# STM32C8.net
KiCad netlist of a schematic drawn in Altium Designer
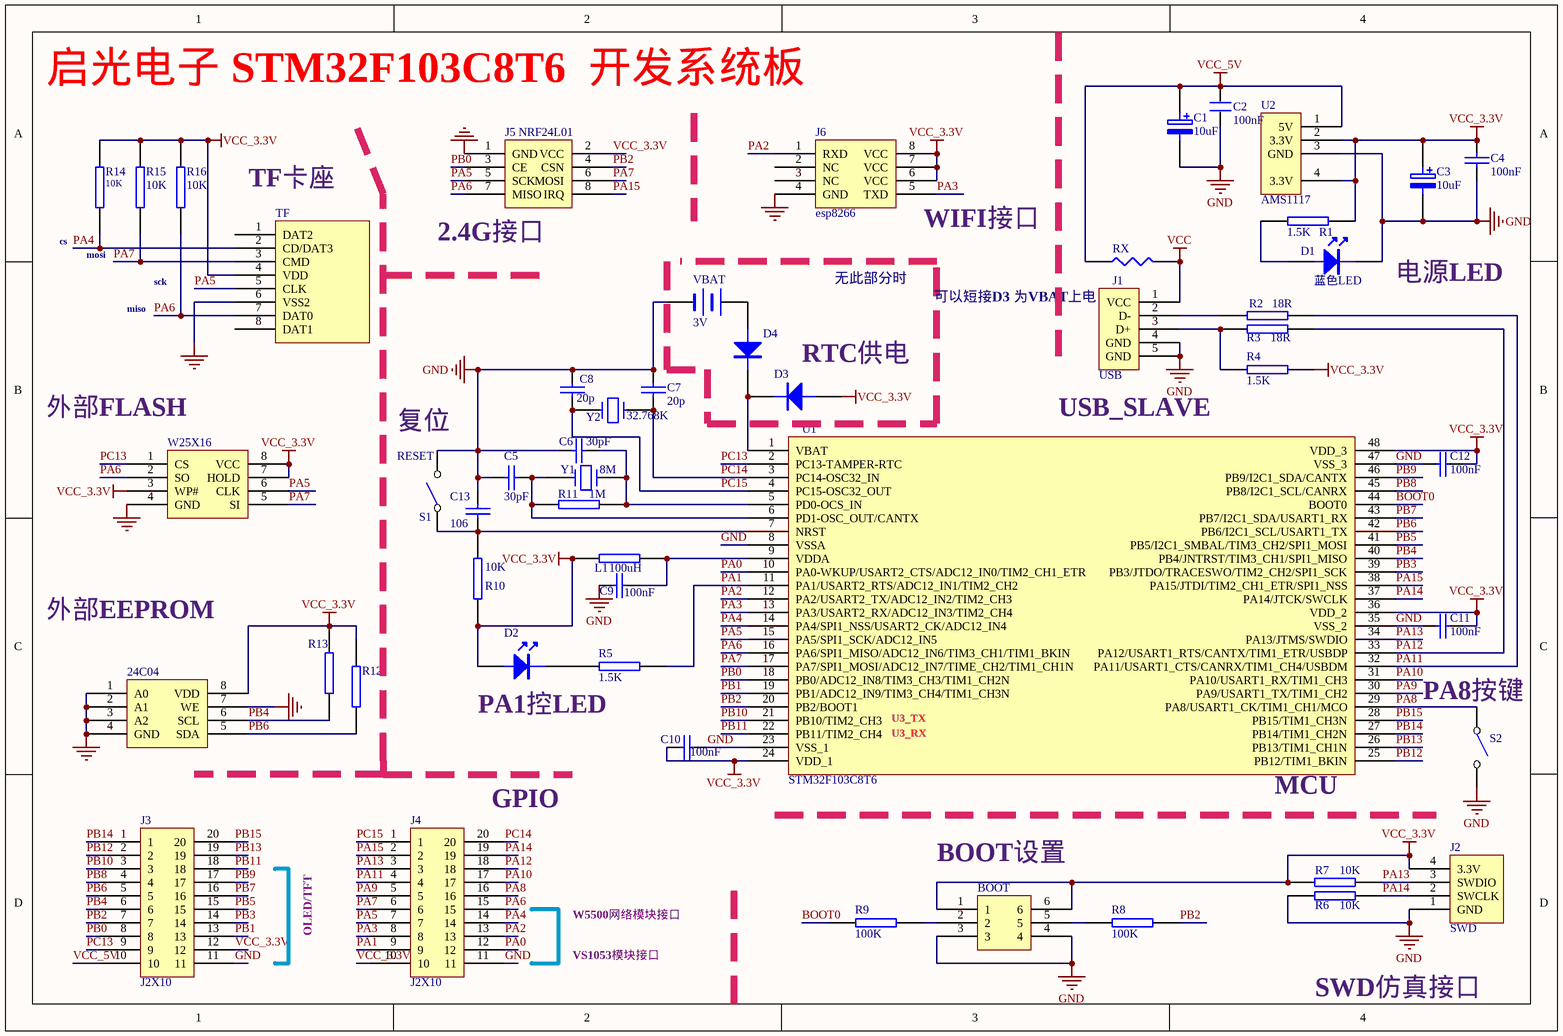
[diagram p0: STM32C8 原理图.SchDoc]

(export (version "E")
  (design (tool "Eeschema 10.0.6"))
  (components
    (comp (ref "24C04") (value "~") (footprint "STC15") (libsource (lib "*") (part "24C")))
    (comp (ref "BOOT") (value "~") (footprint "PZ2*3") (libsource (lib "*") (part "BOOT")))
    (comp (ref "C1")
      (value "10uF")
      (footprint "3216z")
      (description "Electrolytic Capacitor")
      (libsource (lib "原理图器件库(1)") (part "ELECTRO2"))
    )
    (comp (ref "C2") (value "100nF") (footprint "0603C1") (libsource (lib "原理图器件库(1)") (part "C")))
    (comp (ref "C3")
      (value "10uF")
      (footprint "3216z")
      (description "Electrolytic Capacitor")
      (libsource (lib "原理图器件库(1)") (part "ELECTRO2"))
    )
    (comp (ref "C4")
      (value "100nF")
      (footprint "0603C1")
      (description "Capacitor")
      (libsource (lib "原理图器件库") (part "CAP"))
    )
    (comp (ref "C5")
      (value "30pF")
      (footprint "0603C1")
      (description "Capacitor")
      (libsource (lib "*") (part "CAP"))
    )
    (comp (ref "C6")
      (value "30pF")
      (footprint "0603C1")
      (description "Capacitor")
      (libsource (lib "*") (part "CAP"))
    )
    (comp (ref "C7")
      (value "20p")
      (footprint "0603C1")
      (description "Capacitor")
      (libsource (lib "*") (part "CAP"))
    )
    (comp (ref "C8")
      (value "20p")
      (footprint "0603C1")
      (description "Capacitor")
      (libsource (lib "*") (part "CAP"))
    )
    (comp (ref "C9")
      (value "100nF")
      (footprint "0603C1")
      (description "Capacitor")
      (libsource (lib "*") (part "CAP"))
    )
    (comp (ref "C10")
      (value "100nF")
      (footprint "0603C1")
      (description "Capacitor")
      (libsource (lib "*") (part "CAP"))
    )
    (comp (ref "C11")
      (value "100nF")
      (footprint "0603C1")
      (description "Capacitor")
      (libsource (lib "原理图器件库") (part "CAP"))
    )
    (comp (ref "C12")
      (value "100nF")
      (footprint "0603C1")
      (description "Capacitor")
      (libsource (lib "原理图器件库") (part "CAP"))
    )
    (comp (ref "C13")
      (value "106")
      (footprint "0603C1")
      (description "Capacitor")
      (libsource (lib "*") (part "CAP"))
    )
    (comp (ref "D1") (value "蓝色LED") (footprint "LED") (libsource (lib "*") (part "D")))
    (comp (ref "D2") (value "~") (footprint "LED") (libsource (lib "*") (part "D")))
    (comp (ref "D3")
      (value "~")
      (footprint "1206Z")
      (description "Diode")
      (libsource (lib "*") (part "DIODE"))
    )
    (comp (ref "D4")
      (value "~")
      (footprint "1206Z")
      (description "Diode")
      (libsource (lib "*") (part "DIODE"))
    )
    (comp (ref "J1") (value "USB") (footprint "micro-dip") (libsource (lib "原理图器件库(1)") (part "USB")))
    (comp (ref "J2") (value "SWD") (footprint "90p4pz") (libsource (lib "原理图器件库(1)") (part "JSWD")))
    (comp (ref "J3") (value "J2X10") (footprint "PZ2X10") (libsource (lib "原理图器件库(1)") (part "J2X10")))
    (comp (ref "J4") (value "J2X10") (footprint "PZ2X10") (libsource (lib "原理图器件库(1)") (part "J2X10")))
    (comp (ref "J5") (value "NRF24L01") (footprint "NRF24L01") (libsource (lib "*") (part "NRF24L01")))
    (comp (ref "J6") (value "esp8266") (libsource (lib "原理图器件库(1)") (part "esp8266")))
    (comp (ref "L1") (value "100uH") (footprint "0805z") (libsource (lib "*") (part "RES2")))
    (comp (ref "R1") (value "1.5K") (footprint "0603R1") (libsource (lib "*") (part "RES2")))
    (comp (ref "R2") (value "18R") (footprint "0603R1") (libsource (lib "*") (part "RES2")))
    (comp (ref "R3") (value "18R") (footprint "0603R1") (libsource (lib "*") (part "RES2")))
    (comp (ref "R4") (value "1.5K") (footprint "0603R1") (libsource (lib "*") (part "RES2")))
    (comp (ref "R5") (value "1.5K") (footprint "0603R1") (libsource (lib "*") (part "RES2")))
    (comp (ref "R6") (value "10K") (footprint "0603R1") (libsource (lib "*") (part "RES2")))
    (comp (ref "R7") (value "10K") (footprint "0603R1") (libsource (lib "*") (part "RES2")))
    (comp (ref "R8") (value "100K") (footprint "0603R1") (libsource (lib "*") (part "RES2")))
    (comp (ref "R9") (value "100K") (footprint "0603R1") (libsource (lib "*") (part "RES2")))
    (comp (ref "R10") (value "10K") (footprint "0603R1") (libsource (lib "*") (part "RES2")))
    (comp (ref "R11") (value "1M") (footprint "0603R1") (libsource (lib "*") (part "RES2")))
    (comp (ref "R12") (value "~") (footprint "0603R1") (libsource (lib "*") (part "RES2")))
    (comp (ref "R13") (value "~") (footprint "0603R1") (libsource (lib "*") (part "RES2")))
    (comp (ref "R14") (value "10K") (footprint "0805Z") (libsource (lib "*") (part "RES2")))
    (comp (ref "R15") (value "10K") (footprint "0805Z") (libsource (lib "*") (part "RES2")))
    (comp (ref "R16") (value "10K") (footprint "0805Z") (libsource (lib "*") (part "RES2")))
    (comp (ref "RX") (value "~") (footprint "1206z") (libsource (lib "*") (part "RES1")))
    (comp (ref "S1") (value "~") (footprint "FWAJ") (libsource (lib "*") (part "SW-SPST")))
    (comp (ref "S2") (value "~") (footprint "FWAJ") (libsource (lib "*") (part "SW-SPST")))
    (comp (ref "TF") (value "~") (footprint "TF") (libsource (lib "*") (part "MINISD")))
    (comp (ref "U1")
      (value "STM32F103C8T6")
      (footprint "STC12-48")
      (libsource (lib "原理图器件库(1)") (part "STM32C8T6"))
    )
    (comp (ref "U2") (value "AMS1117") (footprint "AMS1117") (libsource (lib "原理图器件库(1)") (part "AMS1117")))
    (comp (ref "VBAT")
      (value "3V")
      (footprint "CR1220")
      (description "Battery")
      (libsource (lib "*") (part "BATTERY"))
    )
    (comp (ref "W25X16") (value "~") (footprint "W25X16") (libsource (lib "*") (part "W25X16")))
    (comp (ref "Y1")
      (value "8M")
      (footprint "YT")
      (description "Crystal")
      (libsource (lib "*") (part "CRYSTAL"))
    )
    (comp (ref "Y2")
      (value "32.768K")
      (footprint "32.768kt")
      (description "Crystal")
      (libsource (lib "*") (part "CRYSTAL"))
    )
  )
  (nets
    (net (code "1") (name "/BOOT0") (class "Default")
      (node (ref "R9") (pin "2") (pinfunction "2_2") (pintype "passive"))
      (node (ref "U1") (pin "44") (pinfunction "BOOT0_44") (pintype "passive"))
    )
    (net (code "2") (name "/PA0") (class "Default")
      (node (ref "J4") (pin "12") (pinfunction "12_12") (pintype "passive"))
      (node (ref "U1") (pin "10") (pinfunction "PA0-WKUP/USART2_CTS/ADC12_IN0/TIM2_CH1_ETR_10") (pintype "passive"))
    )
    (net (code "3") (name "/PA1") (class "Default")
      (node (ref "J4") (pin "9") (pinfunction "9_9") (pintype "passive"))
      (node (ref "R5") (pin "1") (pinfunction "1_1") (pintype "passive"))
      (node (ref "U1") (pin "11") (pinfunction "PA1/USART2_RTS/ADC12_IN1/TIM2_CH2_11") (pintype "passive"))
    )
    (net (code "4") (name "/PA2") (class "Default")
      (node (ref "J4") (pin "13") (pinfunction "13_13") (pintype "passive"))
      (node (ref "J6") (pin "1") (pinfunction "RXD_1") (pintype "passive"))
      (node (ref "U1") (pin "12") (pinfunction "PA2/USART2_TX/ADC12_IN2/TIM2_CH3_12") (pintype "passive"))
    )
    (net (code "5") (name "/PA3") (class "Default")
      (node (ref "J4") (pin "8") (pinfunction "8_8") (pintype "passive"))
      (node (ref "J6") (pin "5") (pinfunction "TXD_5") (pintype "passive"))
      (node (ref "U1") (pin "13") (pinfunction "PA3/USART2_RX/ADC12_IN3/TIM2_CH4_13") (pintype "passive"))
    )
    (net (code "6") (name "/PA4") (class "Default")
      (node (ref "J4") (pin "14") (pinfunction "14_14") (pintype "passive"))
      (node (ref "R14") (pin "2") (pinfunction "2_2") (pintype "passive"))
      (node (ref "TF") (pin "2") (pinfunction "CD/DAT3_2") (pintype "passive"))
      (node (ref "U1") (pin "14") (pinfunction "PA4/SPI1_NSS/USART2_CK/ADC12_IN4_14") (pintype "passive"))
    )
    (net (code "7") (name "/PA5") (class "Default")
      (node (ref "J4") (pin "7") (pinfunction "7_7") (pintype "passive"))
      (node (ref "J5") (pin "5") (pinfunction "SCK_5") (pintype "passive"))
      (node (ref "TF") (pin "5") (pinfunction "CLK_5") (pintype "passive"))
      (node (ref "U1") (pin "15") (pinfunction "PA5/SPI1_SCK/ADC12_IN5_15") (pintype "passive"))
      (node (ref "W25X16") (pin "6") (pinfunction "CLK_6") (pintype "passive"))
    )
    (net (code "8") (name "/PA6") (class "Default")
      (node (ref "J4") (pin "15") (pinfunction "15_15") (pintype "passive"))
      (node (ref "J5") (pin "7") (pinfunction "MISO_7") (pintype "passive"))
      (node (ref "R16") (pin "2") (pinfunction "2_2") (pintype "passive"))
      (node (ref "TF") (pin "7") (pinfunction "DAT0_7") (pintype "passive"))
      (node (ref "U1") (pin "16") (pinfunction "PA6/SPI1_MISO/ADC12_IN6/TIM3_CH1/TIM1_BKIN_16") (pintype "passive"))
      (node (ref "W25X16") (pin "2") (pinfunction "SO_2") (pintype "passive"))
    )
    (net (code "9") (name "/PA7") (class "Default")
      (node (ref "J4") (pin "6") (pinfunction "6_6") (pintype "passive"))
      (node (ref "J5") (pin "6") (pinfunction "MOSI_6") (pintype "passive"))
      (node (ref "R15") (pin "2") (pinfunction "2_2") (pintype "passive"))
      (node (ref "TF") (pin "3") (pinfunction "CMD_3") (pintype "passive"))
      (node (ref "U1") (pin "17") (pinfunction "PA7/SPI1_MOSI/ADC12_IN7/TIME_CH2/TIM1_CH1N_17") (pintype "passive"))
      (node (ref "W25X16") (pin "5") (pinfunction "SI_5") (pintype "passive"))
    )
    (net (code "10") (name "/PA8") (class "Default")
      (node (ref "J4") (pin "16") (pinfunction "16_16") (pintype "passive"))
      (node (ref "S2") (pin "1") (pinfunction "1_1") (pintype "passive"))
      (node (ref "U1") (pin "29") (pinfunction "PA8/USART1_CK/TIM1_CH1/MCO_29") (pintype "passive"))
    )
    (net (code "11") (name "/PA9") (class "Default")
      (node (ref "J4") (pin "5") (pinfunction "5_5") (pintype "passive"))
      (node (ref "U1") (pin "30") (pinfunction "PA9/USART1_TX/TIM1_CH2_30") (pintype "passive"))
    )
    (net (code "12") (name "/PA10") (class "Default")
      (node (ref "J4") (pin "17") (pinfunction "17_17") (pintype "passive"))
      (node (ref "U1") (pin "31") (pinfunction "PA10/USART1_RX/TIM1_CH3_31") (pintype "passive"))
    )
    (net (code "13") (name "/PA11") (class "Default")
      (node (ref "J4") (pin "4") (pinfunction "4_4") (pintype "passive"))
      (node (ref "R2") (pin "2") (pinfunction "2_2") (pintype "passive"))
      (node (ref "U1") (pin "32") (pinfunction "PA11/USART1_CTS/CANRX/TIM1_CH4/USBDM_32") (pintype "passive"))
    )
    (net (code "14") (name "/PA12") (class "Default")
      (node (ref "J4") (pin "18") (pinfunction "18_18") (pintype "passive"))
      (node (ref "R3") (pin "2") (pinfunction "2_2") (pintype "passive"))
      (node (ref "U1") (pin "33") (pinfunction "PA12/USART1_RTS/CANTX/TIM1_ETR/USBDP_33") (pintype "passive"))
    )
    (net (code "15") (name "/PA13") (class "Default")
      (node (ref "J2") (pin "3") (pinfunction "SWDIO_3") (pintype "passive"))
      (node (ref "J4") (pin "3") (pinfunction "3_3") (pintype "passive"))
      (node (ref "R7") (pin "2") (pinfunction "2_2") (pintype "passive"))
      (node (ref "U1") (pin "34") (pinfunction "PA13/JTMS/SWDIO_34") (pintype "passive"))
    )
    (net (code "16") (name "/PA14") (class "Default")
      (node (ref "J2") (pin "2") (pinfunction "SWCLK_2") (pintype "passive"))
      (node (ref "J4") (pin "19") (pinfunction "19_19") (pintype "passive"))
      (node (ref "R6") (pin "2") (pinfunction "2_2") (pintype "passive"))
      (node (ref "U1") (pin "37") (pinfunction "PA14/JTCK/SWCLK_37") (pintype "passive"))
    )
    (net (code "17") (name "/PA15") (class "Default")
      (node (ref "J4") (pin "2") (pinfunction "2_2") (pintype "passive"))
      (node (ref "J5") (pin "8") (pinfunction "IRQ_8") (pintype "passive"))
      (node (ref "U1") (pin "38") (pinfunction "PA15/JTDI/TIM2_CH1_ETR/SPI1_NSS_38") (pintype "passive"))
    )
    (net (code "18") (name "/PB0") (class "Default")
      (node (ref "J3") (pin "8") (pinfunction "8_8") (pintype "passive"))
      (node (ref "J5") (pin "3") (pinfunction "CE_3") (pintype "passive"))
      (node (ref "U1") (pin "18") (pinfunction "PB0/ADC12_IN8/TIM3_CH3/TIM1_CH2N_18") (pintype "passive"))
    )
    (net (code "19") (name "/PB1") (class "Default")
      (node (ref "J3") (pin "13") (pinfunction "13_13") (pintype "passive"))
      (node (ref "U1") (pin "19") (pinfunction "PB1/ADC12_IN9/TIM3_CH4/TIM1_CH3N_19") (pintype "passive"))
    )
    (net (code "20") (name "/PB2") (class "Default")
      (node (ref "J3") (pin "7") (pinfunction "7_7") (pintype "passive"))
      (node (ref "J5") (pin "4") (pinfunction "CSN_4") (pintype "passive"))
      (node (ref "R8") (pin "2") (pinfunction "2_2") (pintype "passive"))
      (node (ref "U1") (pin "20") (pinfunction "PB2/BOOT1_20") (pintype "passive"))
    )
    (net (code "21") (name "/PB3") (class "Default")
      (node (ref "J3") (pin "14") (pinfunction "14_14") (pintype "passive"))
      (node (ref "U1") (pin "39") (pinfunction "PB3/JTDO/TRACESWO/TIM2_CH2/SPI1_SCK_39") (pintype "passive"))
    )
    (net (code "22") (name "/PB4") (class "Default")
      (node (ref "24C04") (pin "6") (pinfunction "SCL_6") (pintype "passive"))
      (node (ref "J3") (pin "6") (pinfunction "6_6") (pintype "passive"))
      (node (ref "R13") (pin "1") (pinfunction "1_1") (pintype "passive"))
      (node (ref "U1") (pin "40") (pinfunction "PB4/JNTRST/TIM3_CH1/SPI1_MISO_40") (pintype "passive"))
    )
    (net (code "23") (name "/PB5") (class "Default")
      (node (ref "J3") (pin "15") (pinfunction "15_15") (pintype "passive"))
      (node (ref "U1") (pin "41") (pinfunction "PB5/I2C1_SMBAL/TIM3_CH2/SPI1_MOSI_41") (pintype "passive"))
    )
    (net (code "24") (name "/PB6") (class "Default")
      (node (ref "24C04") (pin "5") (pinfunction "SDA_5") (pintype "passive"))
      (node (ref "J3") (pin "5") (pinfunction "5_5") (pintype "passive"))
      (node (ref "R12") (pin "1") (pinfunction "1_1") (pintype "passive"))
      (node (ref "U1") (pin "42") (pinfunction "PB6/I2C1_SCL/USART1_TX_42") (pintype "passive"))
    )
    (net (code "25") (name "/PB7") (class "Default")
      (node (ref "J3") (pin "16") (pinfunction "16_16") (pintype "passive"))
      (node (ref "U1") (pin "43") (pinfunction "PB7/I2C1_SDA/USART1_RX_43") (pintype "passive"))
    )
    (net (code "26") (name "/PB8") (class "Default")
      (node (ref "J3") (pin "4") (pinfunction "4_4") (pintype "passive"))
      (node (ref "U1") (pin "45") (pinfunction "PB8/I2C1_SCL/CANRX_45") (pintype "passive"))
    )
    (net (code "27") (name "/PB9") (class "Default")
      (node (ref "J3") (pin "17") (pinfunction "17_17") (pintype "passive"))
      (node (ref "U1") (pin "46") (pinfunction "PB9/I2C1_SDA/CANTX_46") (pintype "passive"))
    )
    (net (code "28") (name "/PB10") (class "Default")
      (node (ref "J3") (pin "3") (pinfunction "3_3") (pintype "passive"))
      (node (ref "U1") (pin "21") (pinfunction "PB10/TIM2_CH3_21") (pintype "passive"))
    )
    (net (code "29") (name "/PB11") (class "Default")
      (node (ref "J3") (pin "18") (pinfunction "18_18") (pintype "passive"))
      (node (ref "U1") (pin "22") (pinfunction "PB11/TIM2_CH4_22") (pintype "passive"))
    )
    (net (code "30") (name "/PB12") (class "Default")
      (node (ref "J3") (pin "2") (pinfunction "2_2") (pintype "passive"))
      (node (ref "U1") (pin "25") (pinfunction "PB12/TIM1_BKIN_25") (pintype "passive"))
    )
    (net (code "31") (name "/PB13") (class "Default")
      (node (ref "J3") (pin "19") (pinfunction "19_19") (pintype "passive"))
      (node (ref "U1") (pin "26") (pinfunction "PB13/TIM1_CH1N_26") (pintype "passive"))
    )
    (net (code "32") (name "/PB14") (class "Default")
      (node (ref "J3") (pin "1") (pinfunction "1_1") (pintype "passive"))
      (node (ref "U1") (pin "27") (pinfunction "PB14/TIM1_CH2N_27") (pintype "passive"))
    )
    (net (code "33") (name "/PB15") (class "Default")
      (node (ref "J3") (pin "20") (pinfunction "20_20") (pintype "passive"))
      (node (ref "U1") (pin "28") (pinfunction "PB15/TIM1_CH3N_28") (pintype "passive"))
    )
    (net (code "34") (name "/PC13") (class "Default")
      (node (ref "J3") (pin "9") (pinfunction "9_9") (pintype "passive"))
      (node (ref "U1") (pin "2") (pinfunction "PC13-TAMPER-RTC_2") (pintype "passive"))
      (node (ref "W25X16") (pin "1") (pinfunction "CS_1") (pintype "passive"))
    )
    (net (code "35") (name "/PC14") (class "Default")
      (node (ref "C7") (pin "1") (pinfunction "1_1") (pintype "passive"))
      (node (ref "J4") (pin "20") (pinfunction "20_20") (pintype "passive"))
      (node (ref "U1") (pin "3") (pinfunction "PC14-OSC32_IN_3") (pintype "passive"))
      (node (ref "Y2") (pin "1") (pinfunction "1_1") (pintype "passive"))
    )
    (net (code "36") (name "/PC15") (class "Default")
      (node (ref "C8") (pin "1") (pinfunction "1_1") (pintype "passive"))
      (node (ref "J4") (pin "1") (pinfunction "1_1") (pintype "passive"))
      (node (ref "U1") (pin "4") (pinfunction "PC15-OSC32_OUT_4") (pintype "passive"))
      (node (ref "Y2") (pin "2") (pinfunction "2_2") (pintype "passive"))
    )
    (net (code "37") (name "GND") (class "Default")
      (node (ref "24C04") (pin "1") (pinfunction "A0_1") (pintype "passive"))
      (node (ref "24C04") (pin "2") (pinfunction "A1_2") (pintype "passive"))
      (node (ref "24C04") (pin "3") (pinfunction "A2_3") (pintype "passive"))
      (node (ref "24C04") (pin "4") (pinfunction "GND_4") (pintype "passive"))
      (node (ref "24C04") (pin "7") (pinfunction "WE_7") (pintype "passive"))
      (node (ref "BOOT") (pin "3") (pinfunction "3_3") (pintype "passive"))
      (node (ref "BOOT") (pin "4") (pinfunction "4_4") (pintype "passive"))
      (node (ref "C1") (pin "2") (pinfunction "2_2") (pintype "passive"))
      (node (ref "C10") (pin "2") (pinfunction "2_2") (pintype "passive"))
      (node (ref "C11") (pin "1") (pinfunction "1_1") (pintype "passive"))
      (node (ref "C12") (pin "1") (pinfunction "1_1") (pintype "passive"))
      (node (ref "C13") (pin "1") (pinfunction "1_1") (pintype "passive"))
      (node (ref "C2") (pin "1") (pintype "passive"))
      (node (ref "C3") (pin "2") (pinfunction "2_2") (pintype "passive"))
      (node (ref "C4") (pin "1") (pinfunction "1_1") (pintype "passive"))
      (node (ref "C5") (pin "2") (pinfunction "2_2") (pintype "passive"))
      (node (ref "C6") (pin "1") (pinfunction "1_1") (pintype "passive"))
      (node (ref "C7") (pin "2") (pinfunction "2_2") (pintype "passive"))
      (node (ref "C8") (pin "2") (pinfunction "2_2") (pintype "passive"))
      (node (ref "C9") (pin "2") (pinfunction "2_2") (pintype "passive"))
      (node (ref "D1") (pin "1") (pinfunction "1_1") (pintype "passive"))
      (node (ref "J1") (pin "4") (pinfunction "GND_4") (pintype "passive"))
      (node (ref "J1") (pin "5") (pinfunction "GND_5") (pintype "passive"))
      (node (ref "J2") (pin "1") (pinfunction "GND_1") (pintype "passive"))
      (node (ref "J3") (pin "11") (pinfunction "11_11") (pintype "passive"))
      (node (ref "J4") (pin "11") (pinfunction "11_11") (pintype "passive"))
      (node (ref "J5") (pin "1") (pinfunction "GND_1") (pintype "passive"))
      (node (ref "J6") (pin "4") (pinfunction "GND_4") (pintype "passive"))
      (node (ref "R6") (pin "1") (pinfunction "1_1") (pintype "passive"))
      (node (ref "S1") (pin "2") (pinfunction "2_2") (pintype "passive"))
      (node (ref "S2") (pin "2") (pinfunction "2_2") (pintype "passive"))
      (node (ref "TF") (pin "6") (pinfunction "VSS2_6") (pintype "passive"))
      (node (ref "U1") (pin "23") (pinfunction "VSS_1_23") (pintype "passive"))
      (node (ref "U1") (pin "35") (pinfunction "VSS_2_35") (pintype "passive"))
      (node (ref "U1") (pin "47") (pinfunction "VSS_3_47") (pintype "passive"))
      (node (ref "U1") (pin "8") (pinfunction "VSSA_8") (pintype "passive"))
      (node (ref "U2") (pin "3") (pinfunction "GND_3") (pintype "passive"))
      (node (ref "VBAT") (pin "2") (pinfunction "-_2") (pintype "passive"))
      (node (ref "W25X16") (pin "4") (pinfunction "GND_4") (pintype "passive"))
    )
    (net (code "38") (name "Net-(BOOT-Pad2)") (class "Default")
      (node (ref "BOOT") (pin "2") (pinfunction "2_2") (pintype "passive"))
      (node (ref "R9") (pin "1") (pinfunction "1_1") (pintype "passive"))
    )
    (net (code "39") (name "Net-(BOOT-Pad5)") (class "Default")
      (node (ref "BOOT") (pin "5") (pinfunction "5_5") (pintype "passive"))
      (node (ref "R8") (pin "1") (pinfunction "1_1") (pintype "passive"))
    )
    (net (code "40") (name "Net-(D1-Pad2)") (class "Default")
      (node (ref "D1") (pin "2") (pinfunction "2_2") (pintype "passive"))
      (node (ref "R1") (pin "1") (pinfunction "1_1") (pintype "passive"))
    )
    (net (code "41") (name "Net-(D2-Pad1)") (class "Default")
      (node (ref "D2") (pin "1") (pinfunction "1_1") (pintype "passive"))
      (node (ref "R5") (pin "2") (pinfunction "2_2") (pintype "passive"))
    )
    (net (code "42") (name "Net-(D3-K)") (class "Default")
      (node (ref "D3") (pin "2") (pinfunction "K_2") (pintype "passive"))
      (node (ref "D4") (pin "2") (pinfunction "K_2") (pintype "passive"))
      (node (ref "U1") (pin "1") (pinfunction "VBAT_1") (pintype "passive"))
    )
    (net (code "43") (name "Net-(D4-A)") (class "Default")
      (node (ref "D4") (pin "1") (pinfunction "A_1") (pintype "passive"))
      (node (ref "VBAT") (pin "1") (pinfunction "+_1") (pintype "passive"))
    )
    (net (code "44") (name "Net-(J1-D+)") (class "Default")
      (node (ref "J1") (pin "3") (pinfunction "D+_3") (pintype "passive"))
      (node (ref "R3") (pin "1") (pinfunction "1_1") (pintype "passive"))
      (node (ref "R4") (pin "2") (pinfunction "2_2") (pintype "passive"))
    )
    (net (code "45") (name "Net-(J1-D-)") (class "Default")
      (node (ref "J1") (pin "2") (pinfunction "D-_2") (pintype "passive"))
      (node (ref "R2") (pin "1") (pinfunction "1_1") (pintype "passive"))
    )
    (net (code "46") (name "Net-(U1-NRST)") (class "Default")
      (node (ref "C13") (pin "2") (pinfunction "2_2") (pintype "passive"))
      (node (ref "R10") (pin "2") (pinfunction "2_2") (pintype "passive"))
      (node (ref "S1") (pin "1") (pinfunction "1_1") (pintype "passive"))
      (node (ref "U1") (pin "7") (pinfunction "NRST_7") (pintype "passive"))
    )
    (net (code "47") (name "Net-(U1-PD0-OCS_IN)") (class "Default")
      (node (ref "C6") (pin "2") (pinfunction "2_2") (pintype "passive"))
      (node (ref "R11") (pin "1") (pinfunction "1_1") (pintype "passive"))
      (node (ref "U1") (pin "5") (pinfunction "PD0-OCS_IN_5") (pintype "passive"))
      (node (ref "Y1") (pin "1") (pinfunction "1_1") (pintype "passive"))
    )
    (net (code "48") (name "Net-(U1-PD1-OSC_OUT{slash}CANTX)") (class "Default")
      (node (ref "C5") (pin "1") (pinfunction "1_1") (pintype "passive"))
      (node (ref "R11") (pin "2") (pinfunction "2_2") (pintype "passive"))
      (node (ref "U1") (pin "6") (pinfunction "PD1-OSC_OUT/CANTX_6") (pintype "passive"))
      (node (ref "Y1") (pin "2") (pinfunction "2_2") (pintype "passive"))
    )
    (net (code "49") (name "Net-(U1-VDDA)") (class "Default")
      (node (ref "C9") (pin "1") (pinfunction "1_1") (pintype "passive"))
      (node (ref "L1") (pin "1") (pinfunction "1_1") (pintype "passive"))
      (node (ref "U1") (pin "9") (pinfunction "VDDA_9") (pintype "passive"))
    )
    (net (code "50") (name "VCC") (class "Default")
      (node (ref "J1") (pin "1") (pinfunction "VCC_1") (pintype "passive"))
      (node (ref "RX") (pin "2") (pinfunction "2_2") (pintype "passive"))
    )
    (net (code "51") (name "VCC_3.3V") (class "Default")
      (node (ref "24C04") (pin "8") (pinfunction "VDD_8") (pintype "passive"))
      (node (ref "BOOT") (pin "1") (pinfunction "1_1") (pintype "passive"))
      (node (ref "BOOT") (pin "6") (pinfunction "6_6") (pintype "passive"))
      (node (ref "C10") (pin "1") (pinfunction "1_1") (pintype "passive"))
      (node (ref "C11") (pin "2") (pinfunction "2_2") (pintype "passive"))
      (node (ref "C12") (pin "2") (pinfunction "2_2") (pintype "passive"))
      (node (ref "C3") (pin "1") (pinfunction "1_1") (pintype "passive"))
      (node (ref "C4") (pin "2") (pinfunction "2_2") (pintype "passive"))
      (node (ref "D2") (pin "2") (pinfunction "2_2") (pintype "passive"))
      (node (ref "D3") (pin "1") (pinfunction "A_1") (pintype "passive"))
      (node (ref "J2") (pin "4") (pinfunction "3.3V_4") (pintype "passive"))
      (node (ref "J3") (pin "12") (pinfunction "12_12") (pintype "passive"))
      (node (ref "J4") (pin "10") (pinfunction "10_10") (pintype "passive"))
      (node (ref "J5") (pin "2") (pinfunction "VCC_2") (pintype "passive"))
      (node (ref "J6") (pin "6") (pinfunction "VCC_6") (pintype "passive"))
      (node (ref "J6") (pin "7") (pinfunction "VCC_7") (pintype "passive"))
      (node (ref "J6") (pin "8") (pinfunction "VCC_8") (pintype "passive"))
      (node (ref "L1") (pin "2") (pinfunction "2_2") (pintype "passive"))
      (node (ref "R1") (pin "2") (pinfunction "2_2") (pintype "passive"))
      (node (ref "R10") (pin "1") (pinfunction "1_1") (pintype "passive"))
      (node (ref "R12") (pin "2") (pinfunction "2_2") (pintype "passive"))
      (node (ref "R13") (pin "2") (pinfunction "2_2") (pintype "passive"))
      (node (ref "R14") (pin "1") (pinfunction "1_1") (pintype "passive"))
      (node (ref "R15") (pin "1") (pinfunction "1_1") (pintype "passive"))
      (node (ref "R16") (pin "1") (pinfunction "1_1") (pintype "passive"))
      (node (ref "R4") (pin "1") (pinfunction "1_1") (pintype "passive"))
      (node (ref "R7") (pin "1") (pinfunction "1_1") (pintype "passive"))
      (node (ref "TF") (pin "4") (pinfunction "VDD_4") (pintype "passive"))
      (node (ref "U1") (pin "24") (pinfunction "VDD_1_24") (pintype "passive"))
      (node (ref "U1") (pin "36") (pinfunction "VDD_2_36") (pintype "passive"))
      (node (ref "U1") (pin "48") (pinfunction "VDD_3_48") (pintype "passive"))
      (node (ref "U2") (pin "2") (pinfunction "3.3V_2") (pintype "passive"))
      (node (ref "U2") (pin "4") (pinfunction "3.3V_4") (pintype "passive"))
      (node (ref "W25X16") (pin "3") (pinfunction "WP#_3") (pintype "passive"))
      (node (ref "W25X16") (pin "7") (pinfunction "HOLD_7") (pintype "passive"))
      (node (ref "W25X16") (pin "8") (pinfunction "VCC_8") (pintype "passive"))
    )
    (net (code "52") (name "VCC_5V") (class "Default")
      (node (ref "C1") (pin "1") (pinfunction "1_1") (pintype "passive"))
      (node (ref "C2") (pin "2") (pintype "passive"))
      (node (ref "J3") (pin "10") (pinfunction "10_10") (pintype "passive"))
      (node (ref "RX") (pin "1") (pinfunction "1_1") (pintype "passive"))
      (node (ref "U2") (pin "1") (pinfunction "5V_1") (pintype "passive"))
    )
    (net (code "53") (name "unconnected-(J6-NC-Pad2)") (class "Default")
      (node (ref "J6") (pin "2") (pinfunction "NC_2") (pintype "passive"))
    )
    (net (code "54") (name "unconnected-(J6-NC-Pad3)") (class "Default")
      (node (ref "J6") (pin "3") (pinfunction "NC_3") (pintype "passive"))
    )
    (net (code "55") (name "unconnected-(TF-DAT1-Pad8)") (class "Default")
      (node (ref "TF") (pin "8") (pinfunction "DAT1_8") (pintype "passive"))
    )
    (net (code "56") (name "unconnected-(TF-DAT2-Pad1)") (class "Default")
      (node (ref "TF") (pin "1") (pinfunction "DAT2_1") (pintype "passive"))
    )
  )
)
